# FC_Conn.net
KiCad netlist of a schematic drawn in Altium Designer
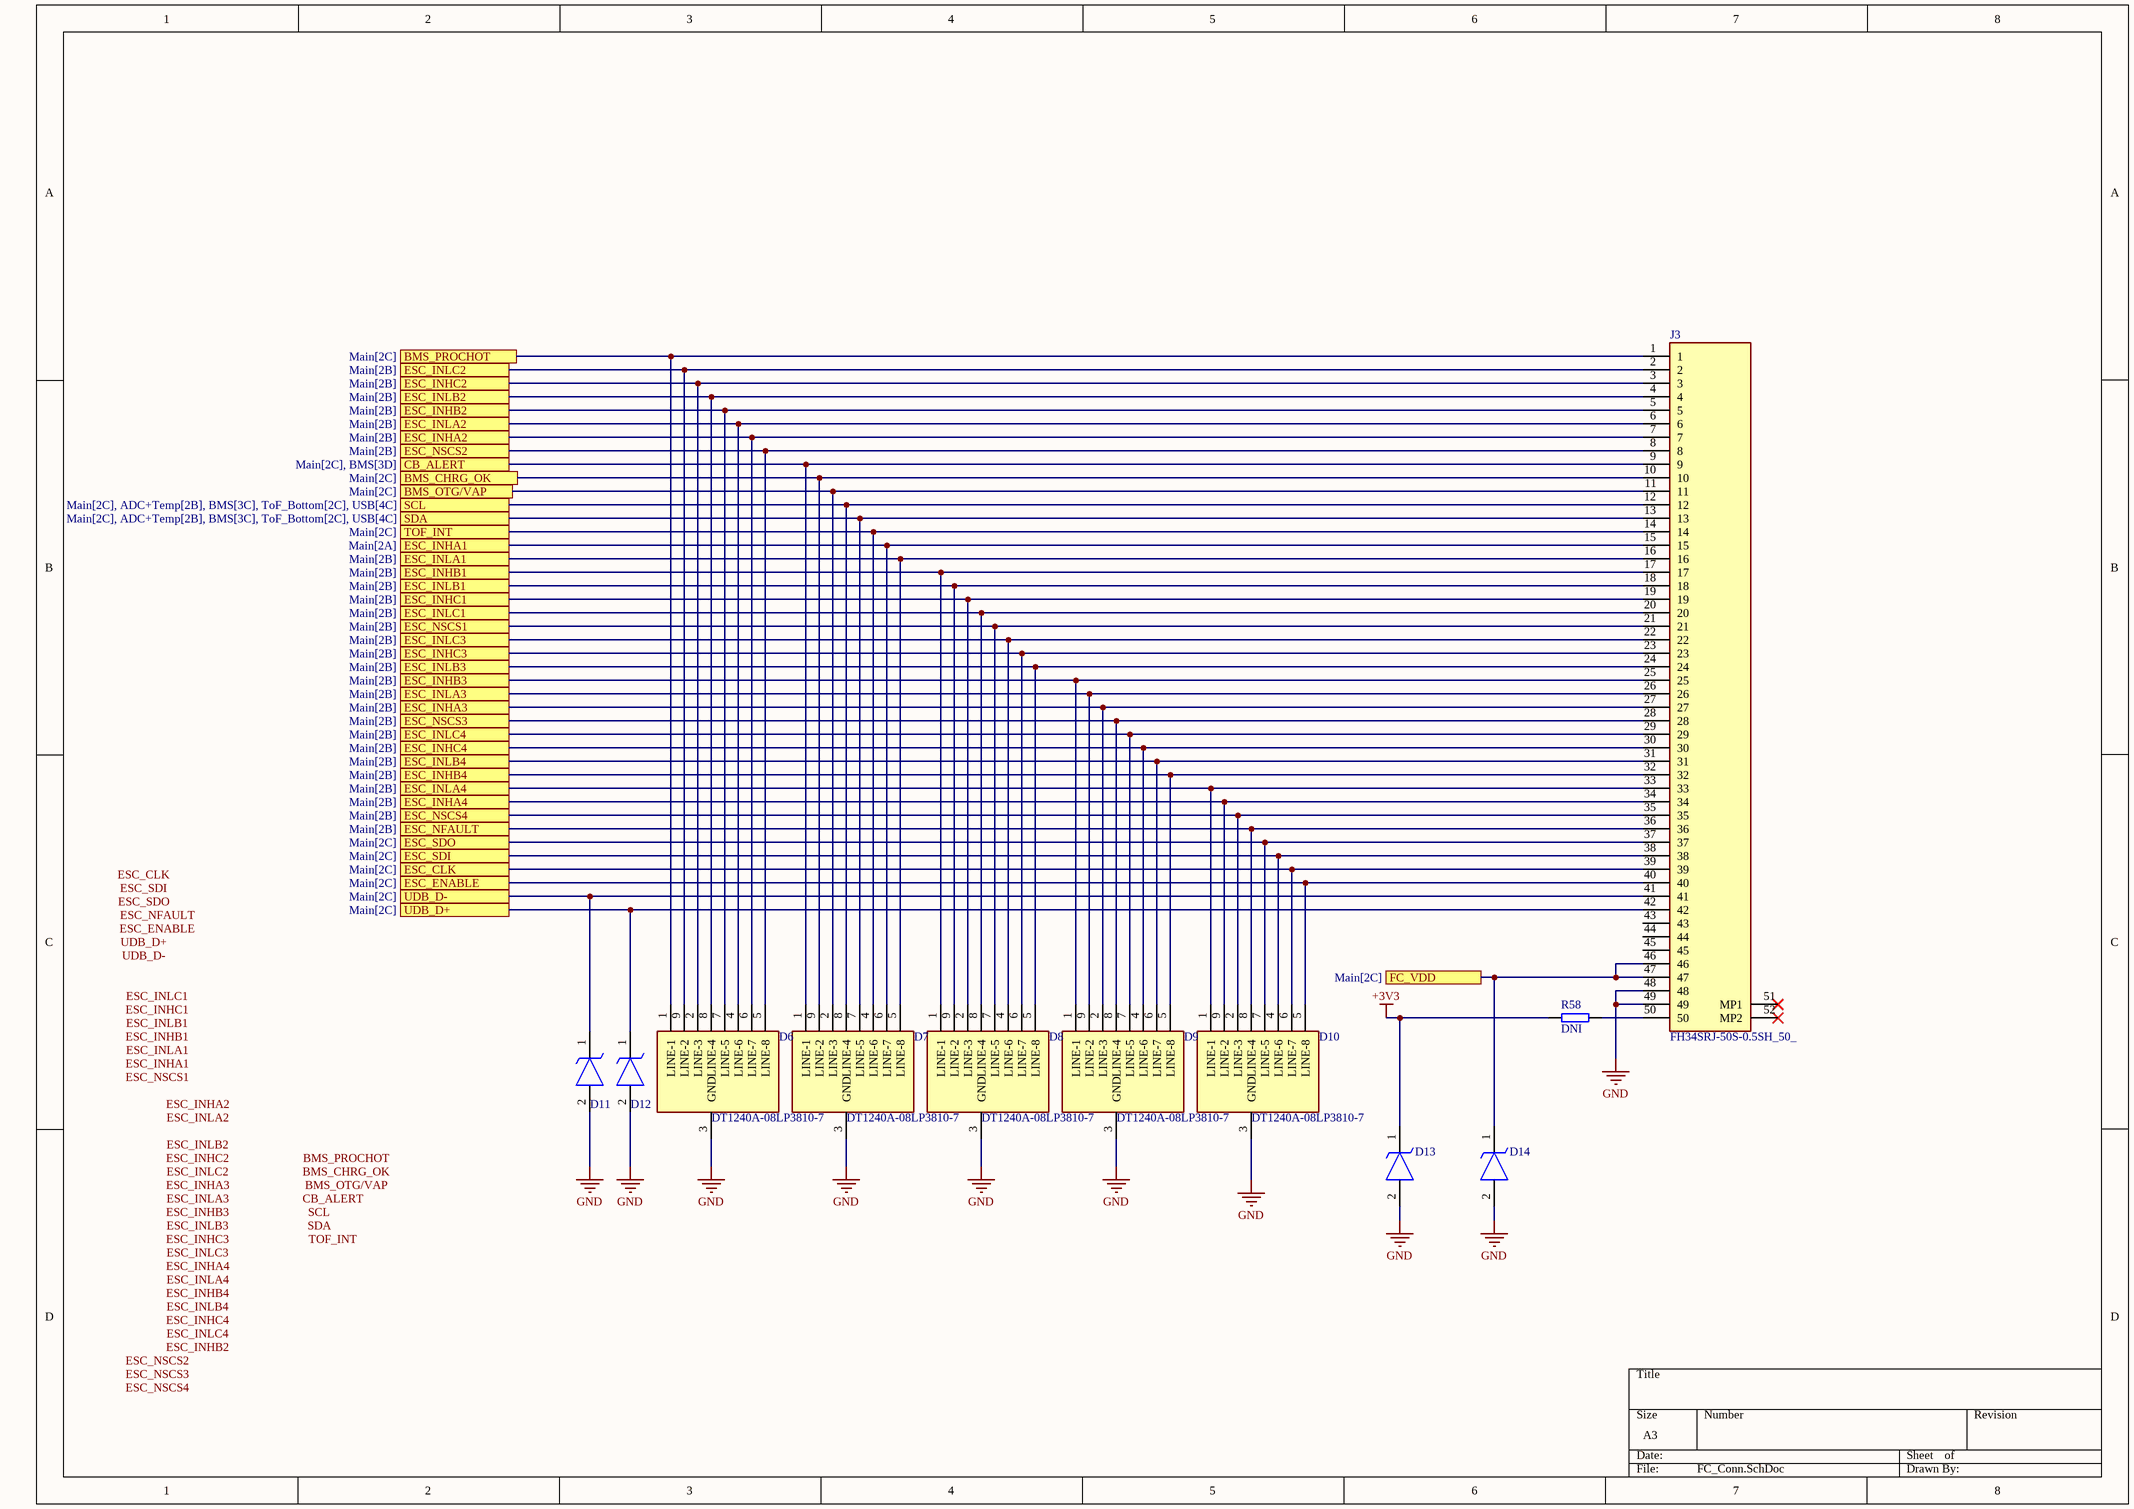
[diagram p0: FC_Conn.SchDoc]

(export (version "E")
  (design (tool "Eeschema 10.0.6"))
  (components
    (comp (ref "D6")
      (value "DT1240A-08LP3810-7")
      (footprint "SamacSys:DT1240A08LP38107")
      (description "TVS Diode (Uni-directional)")
      (fields (field (name "MOUSER PART NUMBER") "621-DT1240A08LP38107"))
      (libsource (lib "SamacSys") (part "DT1240A-08LP3810-7"))
    )
    (comp (ref "D7")
      (value "DT1240A-08LP3810-7")
      (footprint "SamacSys:DT1240A08LP38107")
      (description "TVS Diode (Uni-directional)")
      (fields (field (name "MOUSER PART NUMBER") "621-DT1240A08LP38107"))
      (libsource (lib "SamacSys") (part "DT1240A-08LP3810-7"))
    )
    (comp (ref "D8")
      (value "DT1240A-08LP3810-7")
      (footprint "SamacSys:DT1240A08LP38107")
      (description "TVS Diode (Uni-directional)")
      (fields (field (name "MOUSER PART NUMBER") "621-DT1240A08LP38107"))
      (libsource (lib "SamacSys") (part "DT1240A-08LP3810-7"))
    )
    (comp (ref "D9")
      (value "DT1240A-08LP3810-7")
      (footprint "SamacSys:DT1240A08LP38107")
      (description "TVS Diode (Uni-directional)")
      (fields (field (name "MOUSER PART NUMBER") "621-DT1240A08LP38107"))
      (libsource (lib "SamacSys") (part "DT1240A-08LP3810-7"))
    )
    (comp (ref "D10")
      (value "DT1240A-08LP3810-7")
      (footprint "SamacSys:DT1240A08LP38107")
      (description "TVS Diode (Uni-directional)")
      (fields (field (name "MOUSER PART NUMBER") "621-DT1240A08LP38107"))
      (libsource (lib "SamacSys") (part "DT1240A-08LP3810-7"))
    )
    (comp (ref "D11")
      (value "D1213A-01LP4-7B")
      (footprint "SamacSys:D1213A01LP47B")
      (description "TVS Diode (Uni-directional)")
      (fields (field (name "MOUSER PART NUMBER") "621-D1213A-01LP4-7B"))
      (libsource (lib "*") (part "D1213A-01LP4-7B"))
    )
    (comp (ref "D12")
      (value "D1213A-01LP4-7B")
      (footprint "SamacSys:D1213A01LP47B")
      (description "TVS Diode (Uni-directional)")
      (fields (field (name "MOUSER PART NUMBER") "621-D1213A-01LP4-7B"))
      (libsource (lib "*") (part "D1213A-01LP4-7B"))
    )
    (comp (ref "D13")
      (value "DF2S24FS,L3M")
      (footprint "SamacSys:SODFL1006X45N")
      (description "TVS Diode (Uni-directional)")
      (fields (field (name "MOUSER PART NUMBER") "757-DF2S24FSL3M"))
      (libsource (lib "*") (part "DF2S24FS,L3M"))
    )
    (comp (ref "D14")
      (value "DF2S24FS,L3M")
      (footprint "SamacSys:SODFL1006X45N")
      (description "TVS Diode (Uni-directional)")
      (fields (field (name "MOUSER PART NUMBER") "757-DF2S24FSL3M"))
      (libsource (lib "*") (part "DF2S24FS,L3M"))
    )
    (comp (ref "J3")
      (value "FH34SRJ-50S-0.5SH_50_")
      (footprint "SamacSys:FH34SRJ50S05SH50")
      (description "Connector")
      (fields
        (field (name "MANUFACTURER_PART_NUMBER") "FH34SRJ-50S-0.5SH(50)")
        (field (name "MOUSER PART NUMBER") "798-FH34SRJ50S05SH50")
      )
      (libsource (lib "*") (part "FH34SRJ-50S-0.5SH_50_"))
    )
    (comp (ref "R58")
      (value "DNI")
      (footprint "RES0402")
      (fields (field (name "Comment") "Res0402"))
      (libsource (lib "resistorSMD") (part "Res0402"))
    )
  )
  (nets
    (net (code "1") (name "+3V3") (class "Default")
      (node (ref "D13") (pin "1") (pinfunction "K_1") (pintype "passive"))
      (node (ref "R58") (pin "2") (pinfunction "2_2") (pintype "passive"))
    )
    (net (code "2") (name "/BMS_CHRG_OK") (class "Default")
      (node (ref "D7") (pin "9") (pinfunction "LINE-2_9") (pintype "passive"))
      (node (ref "J3") (pin "10") (pinfunction "10_10") (pintype "passive"))
    )
    (net (code "3") (name "/BMS_OTG{slash}VAP") (class "Default")
      (node (ref "D7") (pin "2") (pinfunction "LINE-3_2") (pintype "passive"))
      (node (ref "J3") (pin "11") (pinfunction "11_11") (pintype "passive"))
    )
    (net (code "4") (name "/BMS_PROCHOT") (class "Default")
      (node (ref "D6") (pin "1") (pinfunction "LINE-1_1") (pintype "passive"))
      (node (ref "J3") (pin "1") (pinfunction "1_1") (pintype "passive"))
    )
    (net (code "5") (name "/CB_ALERT") (class "Default")
      (node (ref "D7") (pin "1") (pinfunction "LINE-1_1") (pintype "passive"))
      (node (ref "J3") (pin "9") (pinfunction "9_9") (pintype "passive"))
    )
    (net (code "6") (name "/ESC_CLK") (class "Default")
      (node (ref "D10") (pin "6") (pinfunction "LINE-7_6") (pintype "passive"))
      (node (ref "J3") (pin "39") (pinfunction "39_39") (pintype "passive"))
    )
    (net (code "7") (name "/ESC_ENABLE") (class "Default")
      (node (ref "D10") (pin "5") (pinfunction "LINE-8_5") (pintype "passive"))
      (node (ref "J3") (pin "40") (pinfunction "40_40") (pintype "passive"))
    )
    (net (code "8") (name "/ESC_INHA1") (class "Default")
      (node (ref "D7") (pin "6") (pinfunction "LINE-7_6") (pintype "passive"))
      (node (ref "J3") (pin "15") (pinfunction "15_15") (pintype "passive"))
    )
    (net (code "9") (name "/ESC_INHA2") (class "Default")
      (node (ref "D6") (pin "6") (pinfunction "LINE-7_6") (pintype "passive"))
      (node (ref "J3") (pin "7") (pinfunction "7_7") (pintype "passive"))
    )
    (net (code "10") (name "/ESC_INHA3") (class "Default")
      (node (ref "D9") (pin "2") (pinfunction "LINE-3_2") (pintype "passive"))
      (node (ref "J3") (pin "27") (pinfunction "27_27") (pintype "passive"))
    )
    (net (code "11") (name "/ESC_INHA4") (class "Default")
      (node (ref "D10") (pin "9") (pinfunction "LINE-2_9") (pintype "passive"))
      (node (ref "J3") (pin "34") (pinfunction "34_34") (pintype "passive"))
    )
    (net (code "12") (name "/ESC_INHB1") (class "Default")
      (node (ref "D8") (pin "1") (pinfunction "LINE-1_1") (pintype "passive"))
      (node (ref "J3") (pin "17") (pinfunction "17_17") (pintype "passive"))
    )
    (net (code "13") (name "/ESC_INHB2") (class "Default")
      (node (ref "D6") (pin "7") (pinfunction "LINE-5_7") (pintype "passive"))
      (node (ref "J3") (pin "5") (pinfunction "5_5") (pintype "passive"))
    )
    (net (code "14") (name "/ESC_INHB3") (class "Default")
      (node (ref "D9") (pin "1") (pinfunction "LINE-1_1") (pintype "passive"))
      (node (ref "J3") (pin "25") (pinfunction "25_25") (pintype "passive"))
    )
    (net (code "15") (name "/ESC_INHB4") (class "Default")
      (node (ref "D9") (pin "5") (pinfunction "LINE-8_5") (pintype "passive"))
      (node (ref "J3") (pin "32") (pinfunction "32_32") (pintype "passive"))
    )
    (net (code "16") (name "/ESC_INHC1") (class "Default")
      (node (ref "D8") (pin "2") (pinfunction "LINE-3_2") (pintype "passive"))
      (node (ref "J3") (pin "19") (pinfunction "19_19") (pintype "passive"))
    )
    (net (code "17") (name "/ESC_INHC2") (class "Default")
      (node (ref "D6") (pin "2") (pinfunction "LINE-3_2") (pintype "passive"))
      (node (ref "J3") (pin "3") (pinfunction "3_3") (pintype "passive"))
    )
    (net (code "18") (name "/ESC_INHC3") (class "Default")
      (node (ref "D8") (pin "6") (pinfunction "LINE-7_6") (pintype "passive"))
      (node (ref "J3") (pin "23") (pinfunction "23_23") (pintype "passive"))
    )
    (net (code "19") (name "/ESC_INHC4") (class "Default")
      (node (ref "D9") (pin "4") (pinfunction "LINE-6_4") (pintype "passive"))
      (node (ref "J3") (pin "30") (pinfunction "30_30") (pintype "passive"))
    )
    (net (code "20") (name "/ESC_INLA1") (class "Default")
      (node (ref "D7") (pin "5") (pinfunction "LINE-8_5") (pintype "passive"))
      (node (ref "J3") (pin "16") (pinfunction "16_16") (pintype "passive"))
    )
    (net (code "21") (name "/ESC_INLA2") (class "Default")
      (node (ref "D6") (pin "4") (pinfunction "LINE-6_4") (pintype "passive"))
      (node (ref "J3") (pin "6") (pinfunction "6_6") (pintype "passive"))
    )
    (net (code "22") (name "/ESC_INLA3") (class "Default")
      (node (ref "D9") (pin "9") (pinfunction "LINE-2_9") (pintype "passive"))
      (node (ref "J3") (pin "26") (pinfunction "26_26") (pintype "passive"))
    )
    (net (code "23") (name "/ESC_INLA4") (class "Default")
      (node (ref "D10") (pin "1") (pinfunction "LINE-1_1") (pintype "passive"))
      (node (ref "J3") (pin "33") (pinfunction "33_33") (pintype "passive"))
    )
    (net (code "24") (name "/ESC_INLB1") (class "Default")
      (node (ref "D8") (pin "9") (pinfunction "LINE-2_9") (pintype "passive"))
      (node (ref "J3") (pin "18") (pinfunction "18_18") (pintype "passive"))
    )
    (net (code "25") (name "/ESC_INLB2") (class "Default")
      (node (ref "D6") (pin "8") (pinfunction "LINE-4_8") (pintype "passive"))
      (node (ref "J3") (pin "4") (pinfunction "4_4") (pintype "passive"))
    )
    (net (code "26") (name "/ESC_INLB3") (class "Default")
      (node (ref "D8") (pin "5") (pinfunction "LINE-8_5") (pintype "passive"))
      (node (ref "J3") (pin "24") (pinfunction "24_24") (pintype "passive"))
    )
    (net (code "27") (name "/ESC_INLB4") (class "Default")
      (node (ref "D9") (pin "6") (pinfunction "LINE-7_6") (pintype "passive"))
      (node (ref "J3") (pin "31") (pinfunction "31_31") (pintype "passive"))
    )
    (net (code "28") (name "/ESC_INLC1") (class "Default")
      (node (ref "D8") (pin "8") (pinfunction "LINE-4_8") (pintype "passive"))
      (node (ref "J3") (pin "20") (pinfunction "20_20") (pintype "passive"))
    )
    (net (code "29") (name "/ESC_INLC2") (class "Default")
      (node (ref "D6") (pin "9") (pinfunction "LINE-2_9") (pintype "passive"))
      (node (ref "J3") (pin "2") (pinfunction "2_2") (pintype "passive"))
    )
    (net (code "30") (name "/ESC_INLC3") (class "Default")
      (node (ref "D8") (pin "4") (pinfunction "LINE-6_4") (pintype "passive"))
      (node (ref "J3") (pin "22") (pinfunction "22_22") (pintype "passive"))
    )
    (net (code "31") (name "/ESC_INLC4") (class "Default")
      (node (ref "D9") (pin "7") (pinfunction "LINE-5_7") (pintype "passive"))
      (node (ref "J3") (pin "29") (pinfunction "29_29") (pintype "passive"))
    )
    (net (code "32") (name "/ESC_NFAULT") (class "Default")
      (node (ref "D10") (pin "8") (pinfunction "LINE-4_8") (pintype "passive"))
      (node (ref "J3") (pin "36") (pinfunction "36_36") (pintype "passive"))
    )
    (net (code "33") (name "/ESC_NSCS1") (class "Default")
      (node (ref "D8") (pin "7") (pinfunction "LINE-5_7") (pintype "passive"))
      (node (ref "J3") (pin "21") (pinfunction "21_21") (pintype "passive"))
    )
    (net (code "34") (name "/ESC_NSCS2") (class "Default")
      (node (ref "D6") (pin "5") (pinfunction "LINE-8_5") (pintype "passive"))
      (node (ref "J3") (pin "8") (pinfunction "8_8") (pintype "passive"))
    )
    (net (code "35") (name "/ESC_NSCS3") (class "Default")
      (node (ref "D9") (pin "8") (pinfunction "LINE-4_8") (pintype "passive"))
      (node (ref "J3") (pin "28") (pinfunction "28_28") (pintype "passive"))
    )
    (net (code "36") (name "/ESC_NSCS4") (class "Default")
      (node (ref "D10") (pin "2") (pinfunction "LINE-3_2") (pintype "passive"))
      (node (ref "J3") (pin "35") (pinfunction "35_35") (pintype "passive"))
    )
    (net (code "37") (name "/ESC_SDI") (class "Default")
      (node (ref "D10") (pin "4") (pinfunction "LINE-6_4") (pintype "passive"))
      (node (ref "J3") (pin "38") (pinfunction "38_38") (pintype "passive"))
    )
    (net (code "38") (name "/ESC_SDO") (class "Default")
      (node (ref "D10") (pin "7") (pinfunction "LINE-5_7") (pintype "passive"))
      (node (ref "J3") (pin "37") (pinfunction "37_37") (pintype "passive"))
    )
    (net (code "39") (name "/FC_VDD") (class "Default")
      (node (ref "D14") (pin "1") (pinfunction "K_1") (pintype "passive"))
      (node (ref "J3") (pin "46") (pinfunction "46_46") (pintype "passive"))
      (node (ref "J3") (pin "47") (pinfunction "47_47") (pintype "passive"))
    )
    (net (code "40") (name "/SCL") (class "Default")
      (node (ref "D7") (pin "8") (pinfunction "LINE-4_8") (pintype "passive"))
      (node (ref "J3") (pin "12") (pinfunction "12_12") (pintype "passive"))
    )
    (net (code "41") (name "/SDA") (class "Default")
      (node (ref "D7") (pin "7") (pinfunction "LINE-5_7") (pintype "passive"))
      (node (ref "J3") (pin "13") (pinfunction "13_13") (pintype "passive"))
    )
    (net (code "42") (name "/TOF_INT") (class "Default")
      (node (ref "D7") (pin "4") (pinfunction "LINE-6_4") (pintype "passive"))
      (node (ref "J3") (pin "14") (pinfunction "14_14") (pintype "passive"))
    )
    (net (code "43") (name "/UDB_D+") (class "Default")
      (node (ref "D12") (pin "1") (pinfunction "K_1") (pintype "passive"))
      (node (ref "J3") (pin "42") (pinfunction "42_42") (pintype "passive"))
    )
    (net (code "44") (name "/UDB_D-") (class "Default")
      (node (ref "D11") (pin "1") (pinfunction "K_1") (pintype "passive"))
      (node (ref "J3") (pin "41") (pinfunction "41_41") (pintype "passive"))
    )
    (net (code "45") (name "GND") (class "Default")
      (node (ref "D10") (pin "3") (pinfunction "GND_3") (pintype "passive"))
      (node (ref "D11") (pin "2") (pinfunction "A_2") (pintype "passive"))
      (node (ref "D12") (pin "2") (pinfunction "A_2") (pintype "passive"))
      (node (ref "D13") (pin "2") (pinfunction "A_2") (pintype "passive"))
      (node (ref "D14") (pin "2") (pinfunction "A_2") (pintype "passive"))
      (node (ref "D6") (pin "3") (pinfunction "GND_3") (pintype "passive"))
      (node (ref "D7") (pin "3") (pinfunction "GND_3") (pintype "passive"))
      (node (ref "D8") (pin "3") (pinfunction "GND_3") (pintype "passive"))
      (node (ref "D9") (pin "3") (pinfunction "GND_3") (pintype "passive"))
      (node (ref "J3") (pin "48") (pinfunction "48_48") (pintype "passive"))
      (node (ref "J3") (pin "49") (pinfunction "49_49") (pintype "passive"))
    )
    (net (code "46") (name "Net-(J3-Pad50)") (class "Default")
      (node (ref "J3") (pin "50") (pinfunction "50_50") (pintype "passive"))
      (node (ref "R58") (pin "1") (pinfunction "1_1") (pintype "passive"))
    )
    (net (code "47") (name "unconnected-(J3-MP1-Pad51)") (class "Default")
      (node (ref "J3") (pin "51") (pinfunction "MP1_51") (pintype "passive+no_connect"))
    )
    (net (code "48") (name "unconnected-(J3-MP2-Pad52)") (class "Default")
      (node (ref "J3") (pin "52") (pinfunction "MP2_52") (pintype "passive+no_connect"))
    )
    (net (code "49") (name "unconnected-(J3-Pad43)") (class "Default")
      (node (ref "J3") (pin "43") (pinfunction "43_43") (pintype "passive"))
    )
    (net (code "50") (name "unconnected-(J3-Pad44)") (class "Default")
      (node (ref "J3") (pin "44") (pinfunction "44_44") (pintype "passive"))
    )
    (net (code "51") (name "unconnected-(J3-Pad45)") (class "Default")
      (node (ref "J3") (pin "45") (pinfunction "45_45") (pintype "passive"))
    )
  )
)
